# as5040.net
KiCad netlist of a schematic drawn in EAGLE
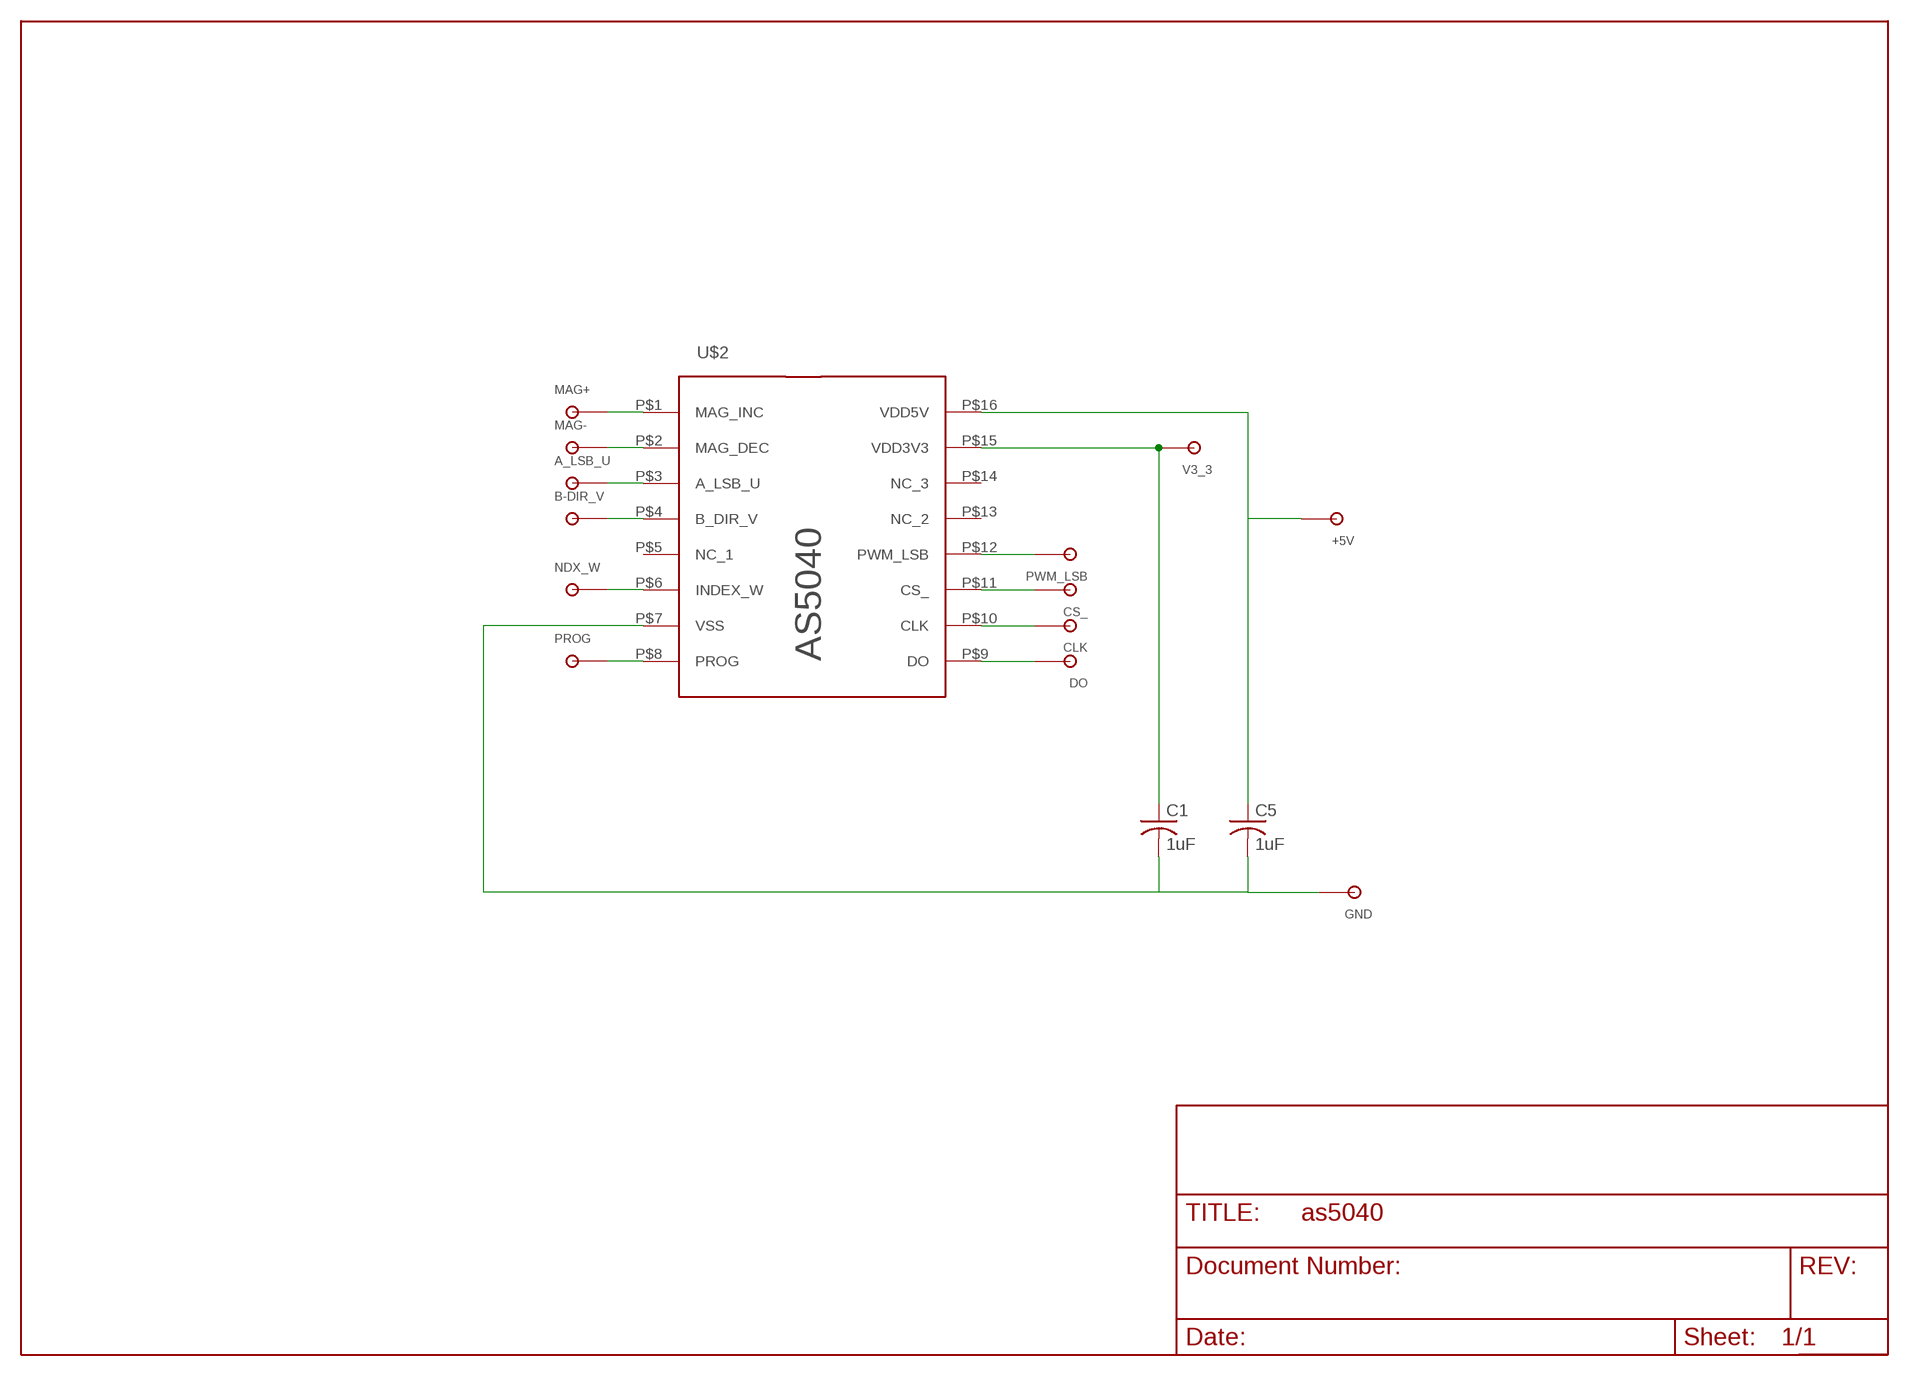
[diagram p0: schematic, sheet 1]

(export (version "E")
  (design (tool "Eeschema 10.0.6"))
  (components
    (comp (ref "+5V")
      (value "TPSOL")
      (footprint "eagle-import:TP_SOL")
      (libsource (lib "eagle-import") (part "TPSOL"))
    )
    (comp (ref "A_LSB_U")
      (value "TPSOL")
      (footprint "eagle-import:TP_SOL")
      (libsource (lib "eagle-import") (part "TPSOL"))
    )
    (comp (ref "B-DIR_V")
      (value "TPSOL")
      (footprint "eagle-import:TP_SOL")
      (libsource (lib "eagle-import") (part "TPSOL"))
    )
    (comp (ref "C1")
      (value "1uF")
      (footprint "eagle-import:C0805K")
      (libsource (lib "eagle-import") (part "C-USC0805K"))
    )
    (comp (ref "C5")
      (value "1uF")
      (footprint "eagle-import:C0805K")
      (libsource (lib "eagle-import") (part "C-USC0805K"))
    )
    (comp (ref "CLK")
      (value "TPSOL")
      (footprint "eagle-import:TP_SOL")
      (libsource (lib "eagle-import") (part "TPSOL"))
    )
    (comp (ref "CS_")
      (value "TPSOL")
      (footprint "eagle-import:TP_SOL")
      (libsource (lib "eagle-import") (part "TPSOL"))
    )
    (comp (ref "DO")
      (value "TPSOL")
      (footprint "eagle-import:TP_SOL")
      (libsource (lib "eagle-import") (part "TPSOL"))
    )
    (comp (ref "GND")
      (value "TPSOL")
      (footprint "eagle-import:TP_SOL")
      (libsource (lib "eagle-import") (part "TPSOL"))
    )
    (comp (ref "MAG+")
      (value "TPSOL")
      (footprint "eagle-import:TP_SOL")
      (libsource (lib "eagle-import") (part "TPSOL"))
    )
    (comp (ref "MAG-")
      (value "TPSOL")
      (footprint "eagle-import:TP_SOL")
      (libsource (lib "eagle-import") (part "TPSOL"))
    )
    (comp (ref "NDX_W")
      (value "TPSOL")
      (footprint "eagle-import:TP_SOL")
      (libsource (lib "eagle-import") (part "TPSOL"))
    )
    (comp (ref "PROG")
      (value "TPSOL")
      (footprint "eagle-import:TP_SOL")
      (libsource (lib "eagle-import") (part "TPSOL"))
    )
    (comp (ref "PWM_LSB")
      (value "TPSOL")
      (footprint "eagle-import:TP_SOL")
      (libsource (lib "eagle-import") (part "TPSOL"))
    )
    (comp (ref "U$2")
      (value "AS5040")
      (footprint "eagle-import:AMS_5040_SPECIAL")
      (libsource (lib "eagle-import") (part "AS5040"))
    )
    (comp (ref "V3_3")
      (value "TPSOL")
      (footprint "eagle-import:TP_SOL")
      (libsource (lib "eagle-import") (part "TPSOL"))
    )
  )
  (nets
    (net (code "1") (name "Net-(U$2-A_LSB_U)") (class "Default")
      (node (ref "A_LSB_U") (pin "P$1") (pinfunction "P$1_P$1") (pintype "bidirectional"))
      (node (ref "U$2") (pin "P$3") (pinfunction "A_LSB_U_P$3") (pintype "bidirectional"))
    )
    (net (code "2") (name "Net-(U$2-B_DIR_V)") (class "Default")
      (node (ref "B-DIR_V") (pin "P$1") (pinfunction "P$1_P$1") (pintype "bidirectional"))
      (node (ref "U$2") (pin "P$4") (pinfunction "B_DIR_V_P$4") (pintype "bidirectional"))
    )
    (net (code "3") (name "Net-(U$2-CLK)") (class "Default")
      (node (ref "CLK") (pin "P$1") (pinfunction "P$1_P$1") (pintype "bidirectional"))
      (node (ref "U$2") (pin "P$10") (pinfunction "CLK_P$10") (pintype "bidirectional"))
    )
    (net (code "4") (name "Net-(U$2-CS_)") (class "Default")
      (node (ref "CS_") (pin "P$1") (pinfunction "P$1_P$1") (pintype "bidirectional"))
      (node (ref "U$2") (pin "P$11") (pinfunction "CS__P$11") (pintype "bidirectional"))
    )
    (net (code "5") (name "Net-(U$2-DO)") (class "Default")
      (node (ref "DO") (pin "P$1") (pinfunction "P$1_P$1") (pintype "bidirectional"))
      (node (ref "U$2") (pin "P$9") (pinfunction "DO_P$9") (pintype "bidirectional"))
    )
    (net (code "6") (name "Net-(U$2-INDEX_W)") (class "Default")
      (node (ref "NDX_W") (pin "P$1") (pinfunction "P$1_P$1") (pintype "bidirectional"))
      (node (ref "U$2") (pin "P$6") (pinfunction "INDEX_W_P$6") (pintype "bidirectional"))
    )
    (net (code "7") (name "Net-(U$2-MAG_DEC)") (class "Default")
      (node (ref "MAG-") (pin "P$1") (pinfunction "P$1_P$1") (pintype "bidirectional"))
      (node (ref "U$2") (pin "P$2") (pinfunction "MAG_DEC_P$2") (pintype "bidirectional"))
    )
    (net (code "8") (name "Net-(U$2-MAG_INC)") (class "Default")
      (node (ref "MAG+") (pin "P$1") (pinfunction "P$1_P$1") (pintype "bidirectional"))
      (node (ref "U$2") (pin "P$1") (pinfunction "MAG_INC_P$1") (pintype "bidirectional"))
    )
    (net (code "9") (name "Net-(U$2-PROG)") (class "Default")
      (node (ref "PROG") (pin "P$1") (pinfunction "P$1_P$1") (pintype "bidirectional"))
      (node (ref "U$2") (pin "P$8") (pinfunction "PROG_P$8") (pintype "bidirectional"))
    )
    (net (code "10") (name "Net-(U$2-PWM_LSB)") (class "Default")
      (node (ref "PWM_LSB") (pin "P$1") (pinfunction "P$1_P$1") (pintype "bidirectional"))
      (node (ref "U$2") (pin "P$12") (pinfunction "PWM_LSB_P$12") (pintype "bidirectional"))
    )
    (net (code "11") (name "Net-(U$2-VDD3V3)") (class "Default")
      (node (ref "C1") (pin "1") (pinfunction "1_1") (pintype "passive"))
      (node (ref "U$2") (pin "P$15") (pinfunction "VDD3V3_P$15") (pintype "bidirectional"))
      (node (ref "V3_3") (pin "P$1") (pinfunction "P$1_P$1") (pintype "bidirectional"))
    )
    (net (code "12") (name "Net-(U$2-VDD5V)") (class "Default")
      (node (ref "+5V") (pin "P$1") (pinfunction "P$1_P$1") (pintype "bidirectional"))
      (node (ref "C5") (pin "1") (pinfunction "1_1") (pintype "passive"))
      (node (ref "U$2") (pin "P$16") (pinfunction "VDD5V_P$16") (pintype "bidirectional"))
    )
    (net (code "13") (name "Net-(U$2-VSS)") (class "Default")
      (node (ref "C1") (pin "2") (pinfunction "2_2") (pintype "passive"))
      (node (ref "C5") (pin "2") (pinfunction "2_2") (pintype "passive"))
      (node (ref "GND") (pin "P$1") (pinfunction "P$1_P$1") (pintype "bidirectional"))
      (node (ref "U$2") (pin "P$7") (pinfunction "VSS_P$7") (pintype "bidirectional"))
    )
    (net (code "14") (name "unconnected-(U$2-NC_1-PadP$5)") (class "Default")
      (node (ref "U$2") (pin "P$5") (pinfunction "NC_1_P$5") (pintype "bidirectional"))
    )
    (net (code "15") (name "unconnected-(U$2-NC_2-PadP$13)") (class "Default")
      (node (ref "U$2") (pin "P$13") (pinfunction "NC_2_P$13") (pintype "bidirectional"))
    )
    (net (code "16") (name "unconnected-(U$2-NC_3-PadP$14)") (class "Default")
      (node (ref "U$2") (pin "P$14") (pinfunction "NC_3_P$14") (pintype "bidirectional"))
    )
  )
)
